# JTAG.net
KiCad netlist of a schematic drawn in Altium Designer
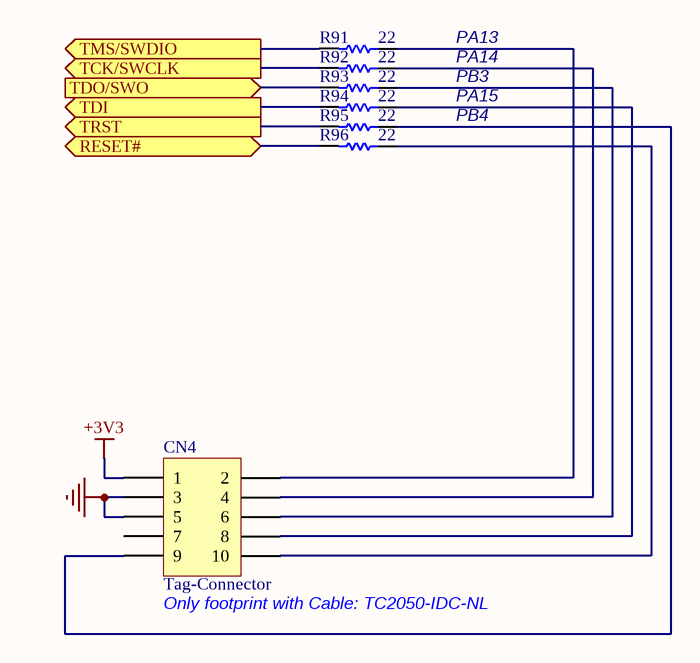
[diagram p0: JTAG.SchDoc]

(export (version "E")
  (design (tool "Eeschema 10.0.6"))
  (components
    (comp (ref "CN4")
      (value "Tag-Connector")
      (footprint "TC2050-IDC-FP")
      (description "Header, 6-Pin, Dual row")
      (fields (field (name "PUBLISHER") "Altium Limited"))
      (libsource (lib "mb1045") (part "Tag-Connector"))
    )
    (comp (ref "R91")
      (value "22")
      (footprint "0603R")
      (description "Resistor")
      (fields (field (name "PUBLISHER") "Altium Limited"))
      (libsource (lib "Miscellaneous Devices") (part "Res1"))
    )
    (comp (ref "R92")
      (value "22")
      (footprint "0603R")
      (description "Resistor")
      (fields (field (name "PUBLISHER") "Altium Limited"))
      (libsource (lib "Miscellaneous Devices") (part "Res1"))
    )
    (comp (ref "R93")
      (value "22")
      (footprint "0603R")
      (description "Resistor")
      (fields (field (name "PUBLISHER") "Altium Limited"))
      (libsource (lib "Miscellaneous Devices") (part "Res1"))
    )
    (comp (ref "R94")
      (value "22")
      (footprint "0603R")
      (description "Resistor")
      (fields (field (name "PUBLISHER") "Altium Limited"))
      (libsource (lib "Miscellaneous Devices") (part "Res1"))
    )
    (comp (ref "R95")
      (value "22")
      (footprint "0603R")
      (description "Resistor")
      (fields (field (name "PUBLISHER") "Altium Limited"))
      (libsource (lib "Miscellaneous Devices") (part "Res1"))
    )
    (comp (ref "R96")
      (value "22")
      (footprint "0603R")
      (description "Resistor")
      (fields (field (name "PUBLISHER") "Altium Limited"))
      (libsource (lib "Miscellaneous Devices") (part "Res1"))
    )
  )
  (nets
    (net (code "1") (name "+3V3") (class "Default")
      (node (ref "CN4") (pin "1") (pinfunction "1_1") (pintype "passive"))
    )
    (net (code "2") (name "/RESET#") (class "Default")
      (node (ref "R96") (pin "2") (pinfunction "2_2") (pintype "passive"))
    )
    (net (code "3") (name "/TCK{slash}SWCLK") (class "Default")
      (node (ref "R92") (pin "2") (pinfunction "2_2") (pintype "passive"))
    )
    (net (code "4") (name "/TDI") (class "Default")
      (node (ref "R94") (pin "2") (pinfunction "2_2") (pintype "passive"))
    )
    (net (code "5") (name "/TDO{slash}SWO") (class "Default")
      (node (ref "R93") (pin "2") (pinfunction "2_2") (pintype "passive"))
    )
    (net (code "6") (name "/TMS{slash}SWDIO") (class "Default")
      (node (ref "R91") (pin "2") (pinfunction "2_2") (pintype "passive"))
    )
    (net (code "7") (name "/TRST") (class "Default")
      (node (ref "R95") (pin "2") (pinfunction "2_2") (pintype "passive"))
    )
    (net (code "8") (name "GND") (class "Default")
      (node (ref "CN4") (pin "3") (pinfunction "3_3") (pintype "passive"))
      (node (ref "CN4") (pin "5") (pinfunction "5_5") (pintype "passive"))
    )
    (net (code "9") (name "Net-(CN4-Pad2)") (class "Default")
      (node (ref "CN4") (pin "2") (pinfunction "2_2") (pintype "passive"))
      (node (ref "R91") (pin "1") (pinfunction "1_1") (pintype "passive"))
    )
    (net (code "10") (name "Net-(CN4-Pad4)") (class "Default")
      (node (ref "CN4") (pin "4") (pinfunction "4_4") (pintype "passive"))
      (node (ref "R92") (pin "1") (pinfunction "1_1") (pintype "passive"))
    )
    (net (code "11") (name "Net-(CN4-Pad6)") (class "Default")
      (node (ref "CN4") (pin "6") (pinfunction "6_6") (pintype "passive"))
      (node (ref "R93") (pin "1") (pinfunction "1_1") (pintype "passive"))
    )
    (net (code "12") (name "Net-(CN4-Pad8)") (class "Default")
      (node (ref "CN4") (pin "8") (pinfunction "8_8") (pintype "passive"))
      (node (ref "R94") (pin "1") (pinfunction "1_1") (pintype "passive"))
    )
    (net (code "13") (name "Net-(CN4-Pad9)") (class "Default")
      (node (ref "CN4") (pin "9") (pinfunction "9_9") (pintype "passive"))
      (node (ref "R95") (pin "1") (pinfunction "1_1") (pintype "passive"))
    )
    (net (code "14") (name "Net-(CN4-Pad10)") (class "Default")
      (node (ref "CN4") (pin "10") (pinfunction "10_10") (pintype "passive"))
      (node (ref "R96") (pin "1") (pinfunction "1_1") (pintype "passive"))
    )
    (net (code "15") (name "unconnected-(CN4-Pad7)") (class "Default")
      (node (ref "CN4") (pin "7") (pinfunction "7_7") (pintype "passive"))
    )
  )
)
